# AVR_Board_4_0_FTDI_USB.net
KiCad netlist of a schematic drawn in Altium Designer
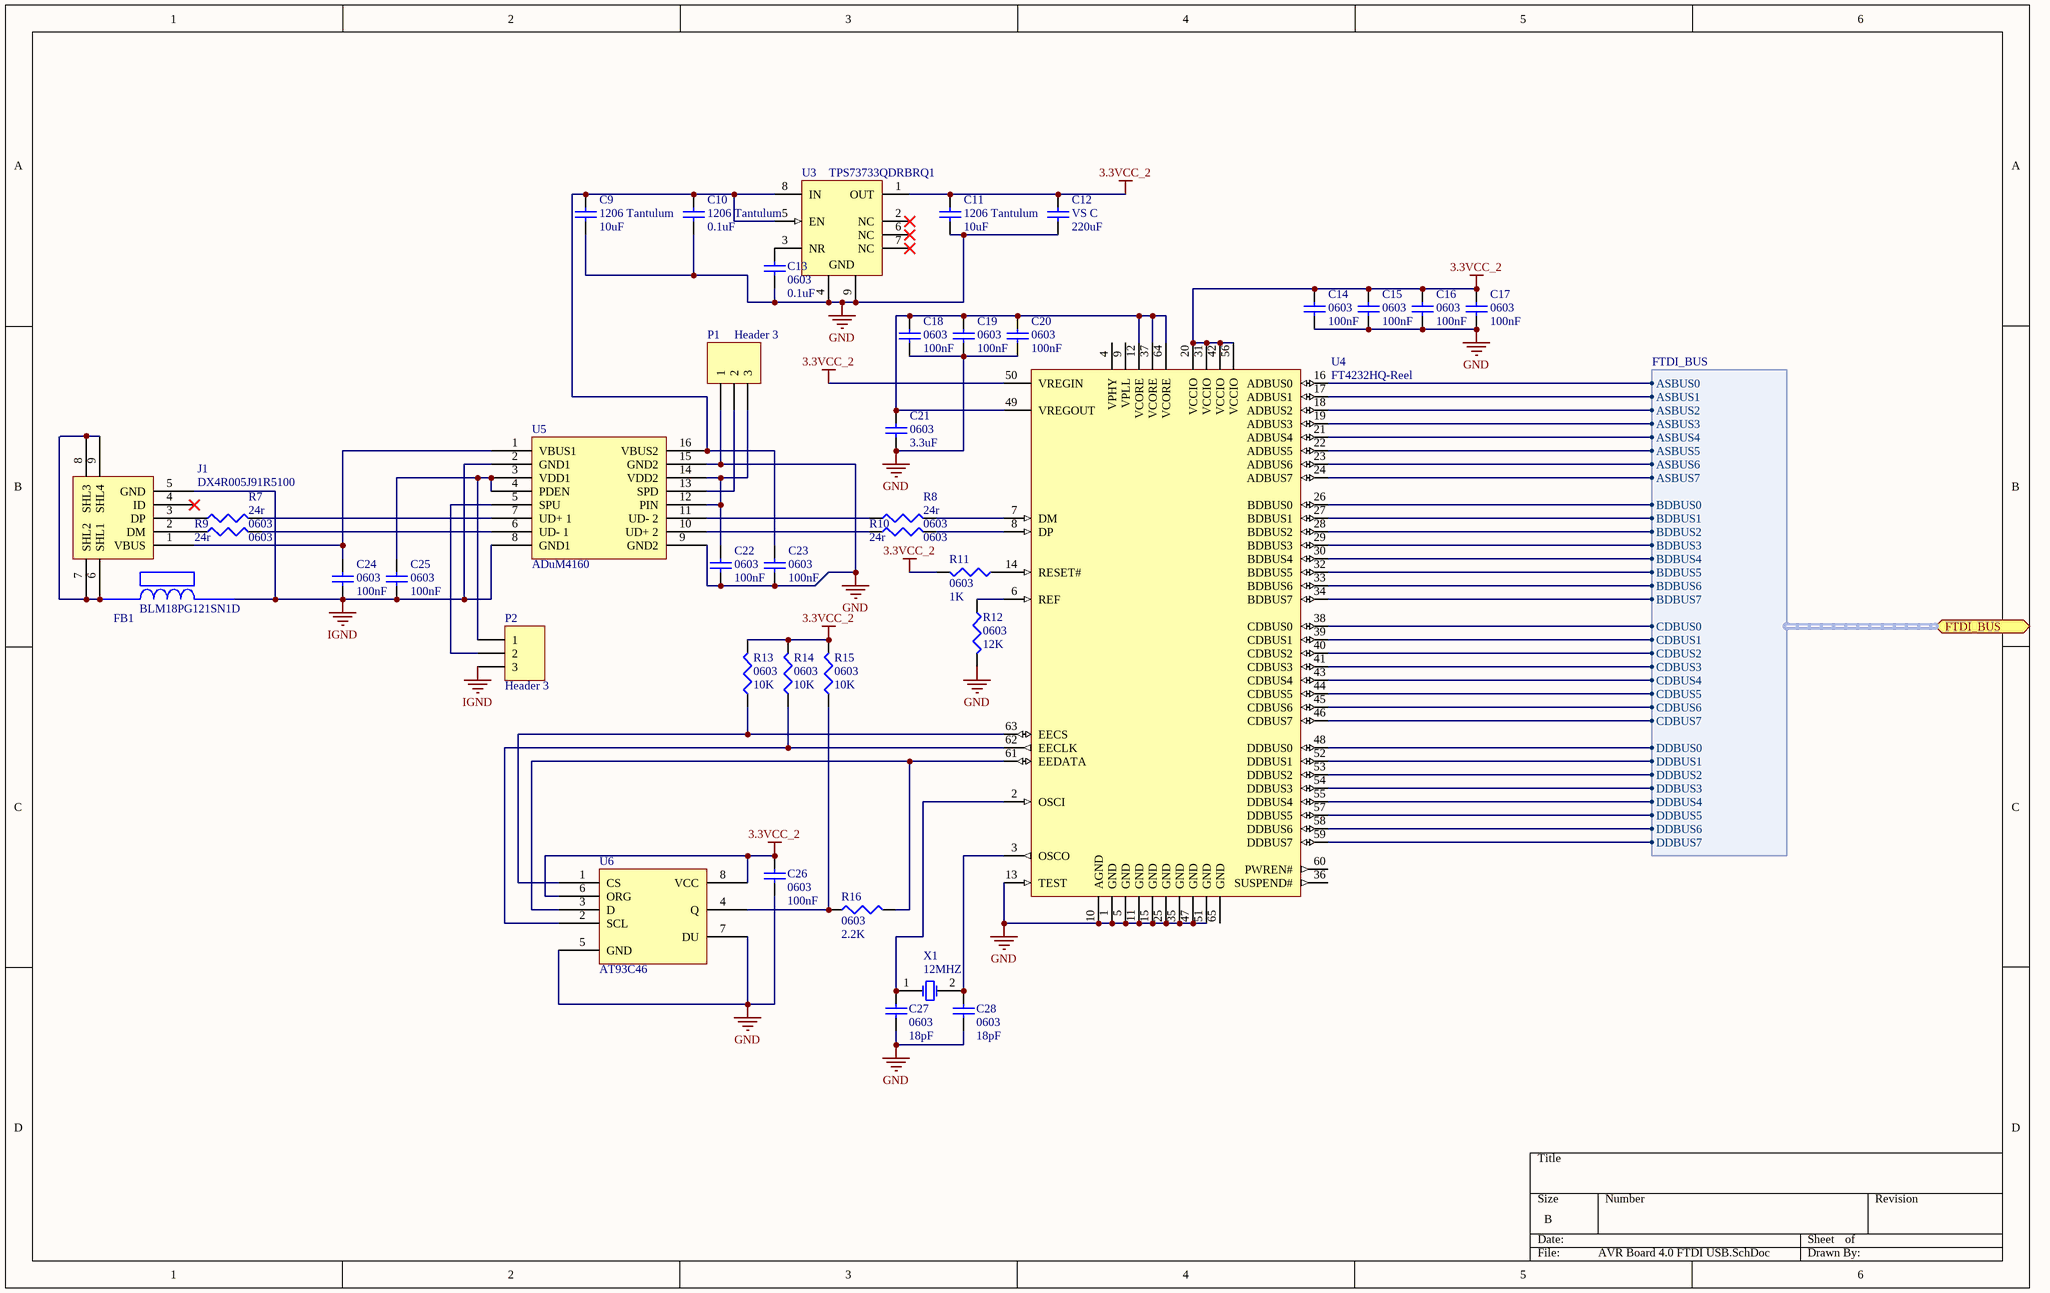
[diagram p0: AVR Board 4.0 FTDI USB.SchDoc]

(export (version "E")
  (design (tool "Eeschema 10.0.6"))
  (components
    (comp (ref "C9")
      (value "1206 Tantulum")
      (footprint "C1206")
      (description "Capacitor (Semiconductor SIM Model)")
      (fields (field (name "ALTIUM_VALUE") "10uF") (field (name "PUBLISHER") "Altium Limited"))
      (libsource (lib "Miscellaneous Devices") (part "Cap Semi"))
    )
    (comp (ref "C10")
      (value "1206 Tantulum")
      (footprint "C1206")
      (description "Capacitor (Semiconductor SIM Model)")
      (fields (field (name "ALTIUM_VALUE") "0.1uF") (field (name "PUBLISHER") "Altium Limited"))
      (libsource (lib "Miscellaneous Devices") (part "Cap Semi"))
    )
    (comp (ref "C11")
      (value "1206 Tantulum")
      (footprint "C1206")
      (description "Capacitor (Semiconductor SIM Model)")
      (fields (field (name "ALTIUM_VALUE") "10uF") (field (name "PUBLISHER") "Altium Limited"))
      (libsource (lib "Miscellaneous Devices") (part "Cap Semi"))
    )
    (comp (ref "C12")
      (value "VS C")
      (footprint "Panasonic VS C")
      (description "Capacitor (Semiconductor SIM Model)")
      (fields (field (name "ALTIUM_VALUE") "220uF") (field (name "PUBLISHER") "Altium Limited"))
      (libsource (lib "Miscellaneous Devices") (part "Cap Semi"))
    )
    (comp (ref "C13")
      (value "0603")
      (footprint "1608[0603]")
      (description "Capacitor (Semiconductor SIM Model)")
      (fields (field (name "ALTIUM_VALUE") "0.1uF") (field (name "PUBLISHER") "Altium Limited"))
      (libsource (lib "Miscellaneous Devices") (part "Cap Semi"))
    )
    (comp (ref "C14")
      (value "0603")
      (footprint "1608[0603]")
      (description "Capacitor (Semiconductor SIM Model)")
      (fields (field (name "ALTIUM_VALUE") "100nF") (field (name "PUBLISHER") "Altium Limited"))
      (libsource (lib "Miscellaneous Devices") (part "Cap Semi"))
    )
    (comp (ref "C15")
      (value "0603")
      (footprint "1608[0603]")
      (description "Capacitor (Semiconductor SIM Model)")
      (fields (field (name "ALTIUM_VALUE") "100nF") (field (name "PUBLISHER") "Altium Limited"))
      (libsource (lib "Miscellaneous Devices") (part "Cap Semi"))
    )
    (comp (ref "C16")
      (value "0603")
      (footprint "1608[0603]")
      (description "Capacitor (Semiconductor SIM Model)")
      (fields (field (name "ALTIUM_VALUE") "100nF") (field (name "PUBLISHER") "Altium Limited"))
      (libsource (lib "Miscellaneous Devices") (part "Cap Semi"))
    )
    (comp (ref "C17")
      (value "0603")
      (footprint "1608[0603]")
      (description "Capacitor (Semiconductor SIM Model)")
      (fields (field (name "ALTIUM_VALUE") "100nF") (field (name "PUBLISHER") "Altium Limited"))
      (libsource (lib "Miscellaneous Devices") (part "Cap Semi"))
    )
    (comp (ref "C18")
      (value "0603")
      (footprint "1608[0603]")
      (description "Capacitor (Semiconductor SIM Model)")
      (fields (field (name "ALTIUM_VALUE") "100nF") (field (name "PUBLISHER") "Altium Limited"))
      (libsource (lib "Miscellaneous Devices") (part "Cap Semi"))
    )
    (comp (ref "C19")
      (value "0603")
      (footprint "1608[0603]")
      (description "Capacitor (Semiconductor SIM Model)")
      (fields (field (name "ALTIUM_VALUE") "100nF") (field (name "PUBLISHER") "Altium Limited"))
      (libsource (lib "Miscellaneous Devices") (part "Cap Semi"))
    )
    (comp (ref "C20")
      (value "0603")
      (footprint "1608[0603]")
      (description "Capacitor (Semiconductor SIM Model)")
      (fields (field (name "ALTIUM_VALUE") "100nF") (field (name "PUBLISHER") "Altium Limited"))
      (libsource (lib "Miscellaneous Devices") (part "Cap Semi"))
    )
    (comp (ref "C21")
      (value "0603")
      (footprint "1608[0603]")
      (description "Capacitor (Semiconductor SIM Model)")
      (fields (field (name "ALTIUM_VALUE") "3.3uF") (field (name "PUBLISHER") "Altium Limited"))
      (libsource (lib "Miscellaneous Devices") (part "Cap Semi"))
    )
    (comp (ref "C22")
      (value "0603")
      (footprint "1608[0603]")
      (description "Capacitor (Semiconductor SIM Model)")
      (fields (field (name "ALTIUM_VALUE") "100nF") (field (name "PUBLISHER") "Altium Limited"))
      (libsource (lib "Miscellaneous Devices") (part "Cap Semi"))
    )
    (comp (ref "C23")
      (value "0603")
      (footprint "1608[0603]")
      (description "Capacitor (Semiconductor SIM Model)")
      (fields (field (name "ALTIUM_VALUE") "100nF") (field (name "PUBLISHER") "Altium Limited"))
      (libsource (lib "Miscellaneous Devices") (part "Cap Semi"))
    )
    (comp (ref "C24")
      (value "0603")
      (footprint "1608[0603]")
      (description "Capacitor (Semiconductor SIM Model)")
      (fields (field (name "ALTIUM_VALUE") "100nF") (field (name "PUBLISHER") "Altium Limited"))
      (libsource (lib "Miscellaneous Devices") (part "Cap Semi"))
    )
    (comp (ref "C25")
      (value "0603")
      (footprint "1608[0603]")
      (description "Capacitor (Semiconductor SIM Model)")
      (fields (field (name "ALTIUM_VALUE") "100nF") (field (name "PUBLISHER") "Altium Limited"))
      (libsource (lib "Miscellaneous Devices") (part "Cap Semi"))
    )
    (comp (ref "C26")
      (value "0603")
      (footprint "1608[0603]")
      (description "Capacitor (Semiconductor SIM Model)")
      (fields (field (name "ALTIUM_VALUE") "100nF") (field (name "PUBLISHER") "Altium Limited"))
      (libsource (lib "Miscellaneous Devices") (part "Cap Semi"))
    )
    (comp (ref "C27")
      (value "0603")
      (footprint "1608[0603]")
      (description "Capacitor (Semiconductor SIM Model)")
      (fields (field (name "ALTIUM_VALUE") "18pF") (field (name "PUBLISHER") "Altium Limited"))
      (libsource (lib "Miscellaneous Devices") (part "Cap Semi"))
    )
    (comp (ref "C28")
      (value "0603")
      (footprint "1608[0603]")
      (description "Capacitor (Semiconductor SIM Model)")
      (fields (field (name "ALTIUM_VALUE") "18pF") (field (name "PUBLISHER") "Altium Limited"))
      (libsource (lib "Miscellaneous Devices") (part "Cap Semi"))
    )
    (comp (ref "FB1")
      (value "BLM18PG121SN1D")
      (footprint "BLM18PG121SN1D")
      (libsource (lib "Adams Altium Library") (part "BLM18PG121SN1D"))
    )
    (comp (ref "J1")
      (value "DX4R005J91R5100")
      (footprint "Micro USB Circular Holes Only")
      (description "Micro USB Jack B")
      (libsource (lib "Adams Altium Library") (part "Micro USB"))
    )
    (comp (ref "P1")
      (value "Header 3")
      (footprint "HDR1X3")
      (description "Header, 3-Pin")
      (fields (field (name "PUBLISHER") "Altium Limited"))
      (libsource (lib "") (part "Header 3_1"))
    )
    (comp (ref "P2")
      (value "Header 3")
      (footprint "HDR1X3")
      (description "Header, 3-Pin")
      (fields (field (name "PUBLISHER") "Altium Limited"))
      (libsource (lib "Miscellaneous Connectors") (part "Header 3"))
    )
    (comp (ref "R7")
      (value "0603")
      (footprint "J1-0603")
      (description "Resistor")
      (fields (field (name "ALTIUM_VALUE") "24r") (field (name "PUBLISHER") "Altium Limited"))
      (libsource (lib "Miscellaneous Devices") (part "Res3"))
    )
    (comp (ref "R8")
      (value "0603")
      (footprint "J1-0603")
      (description "Resistor")
      (fields (field (name "ALTIUM_VALUE") "24r") (field (name "PUBLISHER") "Altium Limited"))
      (libsource (lib "Miscellaneous Devices") (part "Res3"))
    )
    (comp (ref "R9")
      (value "0603")
      (footprint "J1-0603")
      (description "Resistor")
      (fields (field (name "ALTIUM_VALUE") "24r") (field (name "PUBLISHER") "Altium Limited"))
      (libsource (lib "Miscellaneous Devices") (part "Res3"))
    )
    (comp (ref "R10")
      (value "0603")
      (footprint "J1-0603")
      (description "Resistor")
      (fields (field (name "ALTIUM_VALUE") "24r") (field (name "PUBLISHER") "Altium Limited"))
      (libsource (lib "Miscellaneous Devices") (part "Res3"))
    )
    (comp (ref "R11")
      (value "0603")
      (footprint "J1-0603")
      (description "Resistor")
      (fields (field (name "ALTIUM_VALUE") "1K") (field (name "PUBLISHER") "Altium Limited"))
      (libsource (lib "Miscellaneous Devices") (part "Res3"))
    )
    (comp (ref "R12")
      (value "0603")
      (footprint "J1-0603")
      (description "Resistor")
      (fields (field (name "ALTIUM_VALUE") "12K") (field (name "PUBLISHER") "Altium Limited"))
      (libsource (lib "Miscellaneous Devices") (part "Res3"))
    )
    (comp (ref "R13")
      (value "0603")
      (footprint "J1-0603")
      (description "Resistor")
      (fields (field (name "ALTIUM_VALUE") "10K") (field (name "PUBLISHER") "Altium Limited"))
      (libsource (lib "Miscellaneous Devices") (part "Res3"))
    )
    (comp (ref "R14")
      (value "0603")
      (footprint "J1-0603")
      (description "Resistor")
      (fields (field (name "ALTIUM_VALUE") "10K") (field (name "PUBLISHER") "Altium Limited"))
      (libsource (lib "Miscellaneous Devices") (part "Res3"))
    )
    (comp (ref "R15")
      (value "0603")
      (footprint "J1-0603")
      (description "Resistor")
      (fields (field (name "ALTIUM_VALUE") "10K") (field (name "PUBLISHER") "Altium Limited"))
      (libsource (lib "Miscellaneous Devices") (part "Res3"))
    )
    (comp (ref "R16")
      (value "0603")
      (footprint "J1-0603")
      (description "Resistor")
      (fields (field (name "ALTIUM_VALUE") "2.2K") (field (name "PUBLISHER") "Altium Limited"))
      (libsource (lib "Miscellaneous Devices") (part "Res3"))
    )
    (comp (ref "U3")
      (value "TPS73733QDRBRQ1")
      (footprint "TI-DRB8-1750X1500TP_V")
      (fields (field (name "MANUFACTURER") "Texas Instruments"))
      (libsource (lib "TI Power Management Linear Regulator Single Channel LDO (400-7500mA)") (part "TPS73733QDRBRQ1"))
    )
    (comp (ref "U4")
      (value "FT4232HQ-Reel")
      (footprint "QFN64_2_N")
      (description "Quad High Speed USB To Multipurpose UART/MPSSE IC, 64-pin QFN, Tape and Reel")
      (fields (field (name "MANUFACTURER") "FTDI"))
      (libsource (lib "FTDI FT Series") (part "FT4232HQ-Reel"))
    )
    (comp (ref "U5")
      (value "ADuM4160")
      (footprint "ADuM4160")
      (description "USB Opto Isolator")
      (libsource (lib "AVR Board 4.0 Symbol Lib") (part "ADuM4160"))
    )
    (comp (ref "U6")
      (value "AT93C46")
      (footprint "SOIC127P600X175-8N")
      (libsource (lib "AVR Board 4.0 Symbol Lib") (part "AT93C46"))
    )
    (comp (ref "X1")
      (value "12MHZ")
      (footprint "radial 4.88")
      (description "Crystal Oscillator")
      (fields (field (name "PUBLISHER") "Altium Limited"))
      (libsource (lib "Miscellaneous Devices") (part "XTAL"))
    )
  )
  (nets
    (net (code "2") (name "/ASBUS0") (class "Default")
      (node (ref "U4") (pin "16") (pinfunction "ADBUS0_16") (pintype "bidirectional"))
    )
    (net (code "3") (name "/ASBUS1") (class "Default")
      (node (ref "U4") (pin "17") (pinfunction "ADBUS1_17") (pintype "bidirectional"))
    )
    (net (code "4") (name "/ASBUS2") (class "Default")
      (node (ref "U4") (pin "18") (pinfunction "ADBUS2_18") (pintype "bidirectional"))
    )
    (net (code "5") (name "/ASBUS3") (class "Default")
      (node (ref "U4") (pin "19") (pinfunction "ADBUS3_19") (pintype "bidirectional"))
    )
    (net (code "6") (name "/ASBUS4") (class "Default")
      (node (ref "U4") (pin "21") (pinfunction "ADBUS4_21") (pintype "bidirectional"))
    )
    (net (code "7") (name "/ASBUS5") (class "Default")
      (node (ref "U4") (pin "22") (pinfunction "ADBUS5_22") (pintype "bidirectional"))
    )
    (net (code "8") (name "/ASBUS6") (class "Default")
      (node (ref "U4") (pin "23") (pinfunction "ADBUS6_23") (pintype "bidirectional"))
    )
    (net (code "9") (name "/ASBUS7") (class "Default")
      (node (ref "U4") (pin "24") (pinfunction "ADBUS7_24") (pintype "bidirectional"))
    )
    (net (code "10") (name "/BDBUS0") (class "Default")
      (node (ref "U4") (pin "26") (pinfunction "BDBUS0_26") (pintype "bidirectional"))
    )
    (net (code "11") (name "/BDBUS1") (class "Default")
      (node (ref "U4") (pin "27") (pinfunction "BDBUS1_27") (pintype "bidirectional"))
    )
    (net (code "12") (name "/BDBUS2") (class "Default")
      (node (ref "U4") (pin "28") (pinfunction "BDBUS2_28") (pintype "bidirectional"))
    )
    (net (code "13") (name "/BDBUS3") (class "Default")
      (node (ref "U4") (pin "29") (pinfunction "BDBUS3_29") (pintype "bidirectional"))
    )
    (net (code "14") (name "/BDBUS4") (class "Default")
      (node (ref "U4") (pin "30") (pinfunction "BDBUS4_30") (pintype "bidirectional"))
    )
    (net (code "15") (name "/BDBUS5") (class "Default")
      (node (ref "U4") (pin "32") (pinfunction "BDBUS5_32") (pintype "bidirectional"))
    )
    (net (code "16") (name "/BDBUS6") (class "Default")
      (node (ref "U4") (pin "33") (pinfunction "BDBUS6_33") (pintype "bidirectional"))
    )
    (net (code "17") (name "/BDBUS7") (class "Default")
      (node (ref "U4") (pin "34") (pinfunction "BDBUS7_34") (pintype "bidirectional"))
    )
    (net (code "18") (name "/CDBUS0") (class "Default")
      (node (ref "U4") (pin "38") (pinfunction "CDBUS0_38") (pintype "bidirectional"))
    )
    (net (code "19") (name "/CDBUS1") (class "Default")
      (node (ref "U4") (pin "39") (pinfunction "CDBUS1_39") (pintype "bidirectional"))
    )
    (net (code "20") (name "/CDBUS2") (class "Default")
      (node (ref "U4") (pin "40") (pinfunction "CDBUS2_40") (pintype "bidirectional"))
    )
    (net (code "21") (name "/CDBUS3") (class "Default")
      (node (ref "U4") (pin "41") (pinfunction "CDBUS3_41") (pintype "bidirectional"))
    )
    (net (code "22") (name "/CDBUS4") (class "Default")
      (node (ref "U4") (pin "43") (pinfunction "CDBUS4_43") (pintype "bidirectional"))
    )
    (net (code "23") (name "/CDBUS5") (class "Default")
      (node (ref "U4") (pin "44") (pinfunction "CDBUS5_44") (pintype "bidirectional"))
    )
    (net (code "24") (name "/CDBUS6") (class "Default")
      (node (ref "U4") (pin "45") (pinfunction "CDBUS6_45") (pintype "bidirectional"))
    )
    (net (code "25") (name "/CDBUS7") (class "Default")
      (node (ref "U4") (pin "46") (pinfunction "CDBUS7_46") (pintype "bidirectional"))
    )
    (net (code "26") (name "/DDBUS0") (class "Default")
      (node (ref "U4") (pin "48") (pinfunction "DDBUS0_48") (pintype "bidirectional"))
    )
    (net (code "27") (name "/DDBUS1") (class "Default")
      (node (ref "U4") (pin "52") (pinfunction "DDBUS1_52") (pintype "bidirectional"))
    )
    (net (code "28") (name "/DDBUS2") (class "Default")
      (node (ref "U4") (pin "53") (pinfunction "DDBUS2_53") (pintype "bidirectional"))
    )
    (net (code "29") (name "/DDBUS3") (class "Default")
      (node (ref "U4") (pin "54") (pinfunction "DDBUS3_54") (pintype "bidirectional"))
    )
    (net (code "30") (name "/DDBUS4") (class "Default")
      (node (ref "U4") (pin "55") (pinfunction "DDBUS4_55") (pintype "bidirectional"))
    )
    (net (code "31") (name "/DDBUS5") (class "Default")
      (node (ref "U4") (pin "57") (pinfunction "DDBUS5_57") (pintype "bidirectional"))
    )
    (net (code "32") (name "/DDBUS6") (class "Default")
      (node (ref "U4") (pin "58") (pinfunction "DDBUS6_58") (pintype "bidirectional"))
    )
    (net (code "33") (name "/DDBUS7") (class "Default")
      (node (ref "U4") (pin "59") (pinfunction "DDBUS7_59") (pintype "bidirectional"))
    )
    (net (code "35") (name "3.3VCC_2") (class "Default")
      (node (ref "C11") (pin "1") (pinfunction "1_1") (pintype "passive"))
      (node (ref "C12") (pin "1") (pinfunction "1_1") (pintype "passive"))
      (node (ref "C14") (pin "2") (pinfunction "2_2") (pintype "passive"))
      (node (ref "C15") (pin "2") (pinfunction "2_2") (pintype "passive"))
      (node (ref "C16") (pin "2") (pinfunction "2_2") (pintype "passive"))
      (node (ref "C17") (pin "2") (pinfunction "2_2") (pintype "passive"))
      (node (ref "C26") (pin "2") (pinfunction "2_2") (pintype "passive"))
      (node (ref "R11") (pin "2") (pinfunction "2_2") (pintype "passive"))
      (node (ref "R13") (pin "2") (pinfunction "2_2") (pintype "passive"))
      (node (ref "R14") (pin "2") (pinfunction "2_2") (pintype "passive"))
      (node (ref "R15") (pin "2") (pinfunction "2_2") (pintype "passive"))
      (node (ref "U3") (pin "1") (pinfunction "OUT_1") (pintype "power_in"))
      (node (ref "U4") (pin "20") (pinfunction "VCCIO_20") (pintype "power_in"))
      (node (ref "U4") (pin "31") (pinfunction "VCCIO_31") (pintype "power_in"))
      (node (ref "U4") (pin "42") (pinfunction "VCCIO_42") (pintype "power_in"))
      (node (ref "U4") (pin "50") (pinfunction "VREGIN_50") (pintype "power_in"))
      (node (ref "U4") (pin "56") (pinfunction "VCCIO_56") (pintype "power_in"))
      (node (ref "U6") (pin "6") (pinfunction "ORG_6") (pintype "passive"))
      (node (ref "U6") (pin "8") (pinfunction "VCC_8") (pintype "passive"))
    )
    (net (code "36") (name "GND") (class "Default")
      (node (ref "C10") (pin "1") (pinfunction "1_1") (pintype "passive"))
      (node (ref "C11") (pin "2") (pinfunction "2_2") (pintype "passive"))
      (node (ref "C12") (pin "2") (pinfunction "2_2") (pintype "passive"))
      (node (ref "C13") (pin "1") (pinfunction "1_1") (pintype "passive"))
      (node (ref "C14") (pin "1") (pinfunction "1_1") (pintype "passive"))
      (node (ref "C15") (pin "1") (pinfunction "1_1") (pintype "passive"))
      (node (ref "C16") (pin "1") (pinfunction "1_1") (pintype "passive"))
      (node (ref "C17") (pin "1") (pinfunction "1_1") (pintype "passive"))
      (node (ref "C18") (pin "1") (pinfunction "1_1") (pintype "passive"))
      (node (ref "C19") (pin "1") (pinfunction "1_1") (pintype "passive"))
      (node (ref "C20") (pin "1") (pinfunction "1_1") (pintype "passive"))
      (node (ref "C21") (pin "1") (pinfunction "1_1") (pintype "passive"))
      (node (ref "C22") (pin "1") (pinfunction "1_1") (pintype "passive"))
      (node (ref "C23") (pin "1") (pinfunction "1_1") (pintype "passive"))
      (node (ref "C26") (pin "1") (pinfunction "1_1") (pintype "passive"))
      (node (ref "C27") (pin "1") (pinfunction "1_1") (pintype "passive"))
      (node (ref "C28") (pin "1") (pinfunction "1_1") (pintype "passive"))
      (node (ref "C9") (pin "2") (pinfunction "2_2") (pintype "passive"))
      (node (ref "P1") (pin "1") (pinfunction "1_1") (pintype "passive"))
      (node (ref "R12") (pin "2") (pinfunction "2_2") (pintype "passive"))
      (node (ref "U3") (pin "4") (pinfunction "GND_4") (pintype "power_in"))
      (node (ref "U3") (pin "9") (pinfunction "GND_9") (pintype "power_in"))
      (node (ref "U4") (pin "1") (pinfunction "GND_1") (pintype "power_in"))
      (node (ref "U4") (pin "10") (pinfunction "AGND_10") (pintype "power_in"))
      (node (ref "U4") (pin "11") (pinfunction "GND_11") (pintype "power_in"))
      (node (ref "U4") (pin "13") (pinfunction "TEST_13") (pintype "input"))
      (node (ref "U4") (pin "15") (pinfunction "GND_15") (pintype "power_in"))
      (node (ref "U4") (pin "25") (pinfunction "GND_25") (pintype "power_in"))
      (node (ref "U4") (pin "35") (pinfunction "GND_35") (pintype "power_in"))
      (node (ref "U4") (pin "47") (pinfunction "GND_47") (pintype "power_in"))
      (node (ref "U4") (pin "5") (pinfunction "GND_5") (pintype "power_in"))
      (node (ref "U4") (pin "51") (pinfunction "GND_51") (pintype "power_in"))
      (node (ref "U5") (pin "15") (pinfunction "GND2_15") (pintype "passive"))
      (node (ref "U5") (pin "9") (pinfunction "GND2_9") (pintype "passive"))
      (node (ref "U6") (pin "5") (pinfunction "GND_5") (pintype "passive"))
      (node (ref "U6") (pin "7") (pinfunction "DU_7") (pintype "passive"))
    )
    (net (code "37") (name "IGND") (class "Default")
      (node (ref "C24") (pin "1") (pinfunction "1_1") (pintype "passive"))
      (node (ref "C25") (pin "1") (pinfunction "1_1") (pintype "passive"))
      (node (ref "FB1") (pin "2") (pinfunction "2_2") (pintype "passive"))
      (node (ref "J1") (pin "5") (pinfunction "GND_5") (pintype "passive"))
      (node (ref "P2") (pin "3") (pinfunction "3_3") (pintype "passive"))
      (node (ref "U5") (pin "2") (pinfunction "GND1_2") (pintype "passive"))
      (node (ref "U5") (pin "8") (pinfunction "GND1_8") (pintype "passive"))
    )
    (net (code "38") (name "Net-(J1-DM)") (class "Default")
      (node (ref "J1") (pin "2") (pinfunction "DM_2") (pintype "passive"))
      (node (ref "R9") (pin "1") (pinfunction "1_1") (pintype "passive"))
    )
    (net (code "39") (name "Net-(J1-DP)") (class "Default")
      (node (ref "J1") (pin "3") (pinfunction "DP_3") (pintype "passive"))
      (node (ref "R7") (pin "1") (pinfunction "1_1") (pintype "passive"))
    )
    (net (code "40") (name "Net-(J1-SHL1)") (class "Default")
      (node (ref "FB1") (pin "1") (pinfunction "1_1") (pintype "passive"))
      (node (ref "J1") (pin "6") (pinfunction "SHL1_6") (pintype "passive"))
      (node (ref "J1") (pin "7") (pinfunction "SHL2_7") (pintype "passive"))
      (node (ref "J1") (pin "8") (pinfunction "SHL3_8") (pintype "passive"))
      (node (ref "J1") (pin "9") (pinfunction "SHL4_9") (pintype "passive"))
    )
    (net (code "41") (name "Net-(J1-VBUS)") (class "Default")
      (node (ref "C24") (pin "2") (pinfunction "2_2") (pintype "passive"))
      (node (ref "J1") (pin "1") (pinfunction "VBUS_1") (pintype "passive"))
      (node (ref "U5") (pin "1") (pinfunction "VBUS1_1") (pintype "passive"))
    )
    (net (code "42") (name "Net-(U3-EN)") (class "Default")
      (node (ref "C10") (pin "2") (pinfunction "2_2") (pintype "passive"))
      (node (ref "C23") (pin "2") (pinfunction "2_2") (pintype "passive"))
      (node (ref "C9") (pin "1") (pinfunction "1_1") (pintype "passive"))
      (node (ref "U3") (pin "5") (pinfunction "EN_5") (pintype "input"))
      (node (ref "U3") (pin "8") (pinfunction "IN_8") (pintype "power_in"))
      (node (ref "U5") (pin "16") (pinfunction "VBUS2_16") (pintype "passive"))
    )
    (net (code "43") (name "Net-(U3-NR)") (class "Default")
      (node (ref "C13") (pin "2") (pinfunction "2_2") (pintype "passive"))
      (node (ref "U3") (pin "3") (pinfunction "NR_3") (pintype "passive"))
    )
    (net (code "44") (name "Net-(U4-DM)") (class "Default")
      (node (ref "R8") (pin "2") (pinfunction "2_2") (pintype "passive"))
      (node (ref "U4") (pin "7") (pinfunction "DM_7") (pintype "input"))
    )
    (net (code "45") (name "Net-(U4-DP)") (class "Default")
      (node (ref "R10") (pin "2") (pinfunction "2_2") (pintype "passive"))
      (node (ref "U4") (pin "8") (pinfunction "DP_8") (pintype "input"))
    )
    (net (code "46") (name "Net-(U4-EECLK)") (class "Default")
      (node (ref "R14") (pin "1") (pinfunction "1_1") (pintype "passive"))
      (node (ref "U4") (pin "62") (pinfunction "EECLK_62") (pintype "output"))
      (node (ref "U6") (pin "2") (pinfunction "SCL_2") (pintype "passive"))
    )
    (net (code "47") (name "Net-(U4-EECS)") (class "Default")
      (node (ref "R13") (pin "1") (pinfunction "1_1") (pintype "passive"))
      (node (ref "U4") (pin "63") (pinfunction "EECS_63") (pintype "bidirectional"))
      (node (ref "U6") (pin "1") (pinfunction "CS_1") (pintype "passive"))
    )
    (net (code "48") (name "Net-(U4-EEDATA)") (class "Default")
      (node (ref "R16") (pin "2") (pinfunction "2_2") (pintype "passive"))
      (node (ref "U4") (pin "61") (pinfunction "EEDATA_61") (pintype "bidirectional"))
      (node (ref "U6") (pin "3") (pinfunction "D_3") (pintype "passive"))
    )
    (net (code "49") (name "Net-(U4-OSCI)") (class "Default")
      (node (ref "C27") (pin "2") (pinfunction "2_2") (pintype "passive"))
      (node (ref "U4") (pin "2") (pinfunction "OSCI_2") (pintype "input"))
      (node (ref "X1") (pin "1") (pinfunction "OSC1_1") (pintype "passive"))
    )
    (net (code "50") (name "Net-(U4-OSCO)") (class "Default")
      (node (ref "C28") (pin "2") (pinfunction "2_2") (pintype "passive"))
      (node (ref "U4") (pin "3") (pinfunction "OSCO_3") (pintype "output"))
      (node (ref "X1") (pin "2") (pinfunction "OSC2_2") (pintype "passive"))
    )
    (net (code "51") (name "Net-(U4-REF)") (class "Default")
      (node (ref "R12") (pin "1") (pinfunction "1_1") (pintype "passive"))
      (node (ref "U4") (pin "6") (pinfunction "REF_6") (pintype "input"))
    )
    (net (code "52") (name "Net-(U4-RESET#)") (class "Default")
      (node (ref "R11") (pin "1") (pinfunction "1_1") (pintype "passive"))
      (node (ref "U4") (pin "14") (pinfunction "RESET#_14") (pintype "input"))
    )
    (net (code "53") (name "Net-(U4-VREGOUT)") (class "Default")
      (node (ref "C18") (pin "2") (pinfunction "2_2") (pintype "passive"))
      (node (ref "C19") (pin "2") (pinfunction "2_2") (pintype "passive"))
      (node (ref "C20") (pin "2") (pinfunction "2_2") (pintype "passive"))
      (node (ref "C21") (pin "2") (pinfunction "2_2") (pintype "passive"))
      (node (ref "U4") (pin "12") (pinfunction "VCORE_12") (pintype "power_in"))
      (node (ref "U4") (pin "37") (pinfunction "VCORE_37") (pintype "power_in"))
      (node (ref "U4") (pin "49") (pinfunction "VREGOUT_49") (pintype "power_in"))
      (node (ref "U4") (pin "64") (pinfunction "VCORE_64") (pintype "power_in"))
    )
    (net (code "54") (name "Net-(U5-PDEN)") (class "Default")
      (node (ref "C25") (pin "2") (pinfunction "2_2") (pintype "passive"))
      (node (ref "P2") (pin "1") (pinfunction "1_1") (pintype "passive"))
      (node (ref "U5") (pin "3") (pinfunction "VDD1_3") (pintype "passive"))
      (node (ref "U5") (pin "4") (pinfunction "PDEN_4") (pintype "passive"))
    )
    (net (code "55") (name "Net-(U5-PIN)") (class "Default")
      (node (ref "C22") (pin "2") (pinfunction "2_2") (pintype "passive"))
      (node (ref "P1") (pin "3") (pinfunction "3_3") (pintype "passive"))
      (node (ref "U5") (pin "12") (pinfunction "PIN_12") (pintype "passive"))
      (node (ref "U5") (pin "14") (pinfunction "VDD2_14") (pintype "passive"))
    )
    (net (code "56") (name "Net-(U5-SPD)") (class "Default")
      (node (ref "P1") (pin "2") (pinfunction "2_2") (pintype "passive"))
      (node (ref "U5") (pin "13") (pinfunction "SPD_13") (pintype "passive"))
    )
    (net (code "57") (name "Net-(U5-SPU)") (class "Default")
      (node (ref "P2") (pin "2") (pinfunction "2_2") (pintype "passive"))
      (node (ref "U5") (pin "5") (pinfunction "SPU_5") (pintype "passive"))
    )
    (net (code "58") (name "Net-(U5-UD+_1)") (class "Default")
      (node (ref "R7") (pin "2") (pinfunction "2_2") (pintype "passive"))
      (node (ref "U5") (pin "7") (pinfunction "UD+_1_7") (pintype "passive"))
    )
    (net (code "59") (name "Net-(U5-UD+_2)") (class "Default")
      (node (ref "R10") (pin "1") (pinfunction "1_1") (pintype "passive"))
      (node (ref "U5") (pin "10") (pinfunction "UD+_2_10") (pintype "passive"))
    )
    (net (code "60") (name "Net-(U5-UD-_1)") (class "Default")
      (node (ref "R9") (pin "2") (pinfunction "2_2") (pintype "passive"))
      (node (ref "U5") (pin "6") (pinfunction "UD-_1_6") (pintype "passive"))
    )
    (net (code "61") (name "Net-(U5-UD-_2)") (class "Default")
      (node (ref "R8") (pin "1") (pinfunction "1_1") (pintype "passive"))
      (node (ref "U5") (pin "11") (pinfunction "UD-_2_11") (pintype "passive"))
    )
    (net (code "62") (name "Net-(U6-Q)") (class "Default")
      (node (ref "R15") (pin "1") (pinfunction "1_1") (pintype "passive"))
      (node (ref "R16") (pin "1") (pinfunction "1_1") (pintype "passive"))
      (node (ref "U6") (pin "4") (pinfunction "Q_4") (pintype "passive"))
    )
    (net (code "63") (name "unconnected-(J1-ID-Pad4)") (class "Default")
      (node (ref "J1") (pin "4") (pinfunction "ID_4") (pintype "passive+no_connect"))
    )
    (net (code "64") (name "unconnected-(U3-NC-Pad2)") (class "Default")
      (node (ref "U3") (pin "2") (pinfunction "NC_2") (pintype "passive+no_connect"))
    )
    (net (code "65") (name "unconnected-(U3-NC-Pad6)") (class "Default")
      (node (ref "U3") (pin "6") (pinfunction "NC_6") (pintype "passive+no_connect"))
    )
    (net (code "66") (name "unconnected-(U3-NC-Pad7)") (class "Default")
      (node (ref "U3") (pin "7") (pinfunction "NC_7") (pintype "passive+no_connect"))
    )
    (net (code "67") (name "unconnected-(U4-GND-Pad65)") (class "Default")
      (node (ref "U4") (pin "65") (pinfunction "GND_65") (pintype "power_in"))
    )
    (net (code "68") (name "unconnected-(U4-PWREN#-Pad60)") (class "Default")
      (node (ref "U4") (pin "60") (pinfunction "PWREN#_60") (pintype "output"))
    )
    (net (code "69") (name "unconnected-(U4-SUSPEND#-Pad36)") (class "Default")
      (node (ref "U4") (pin "36") (pinfunction "SUSPEND#_36") (pintype "output"))
    )
    (net (code "70") (name "unconnected-(U4-VPHY-Pad4)") (class "Default")
      (node (ref "U4") (pin "4") (pinfunction "VPHY_4") (pintype "power_in"))
    )
    (net (code "71") (name "unconnected-(U4-VPLL-Pad9)") (class "Default")
      (node (ref "U4") (pin "9") (pinfunction "VPLL_9") (pintype "power_in"))
    )
  )
)
